# RectifierPartOne.net
KiCad netlist of a schematic drawn in EAGLE
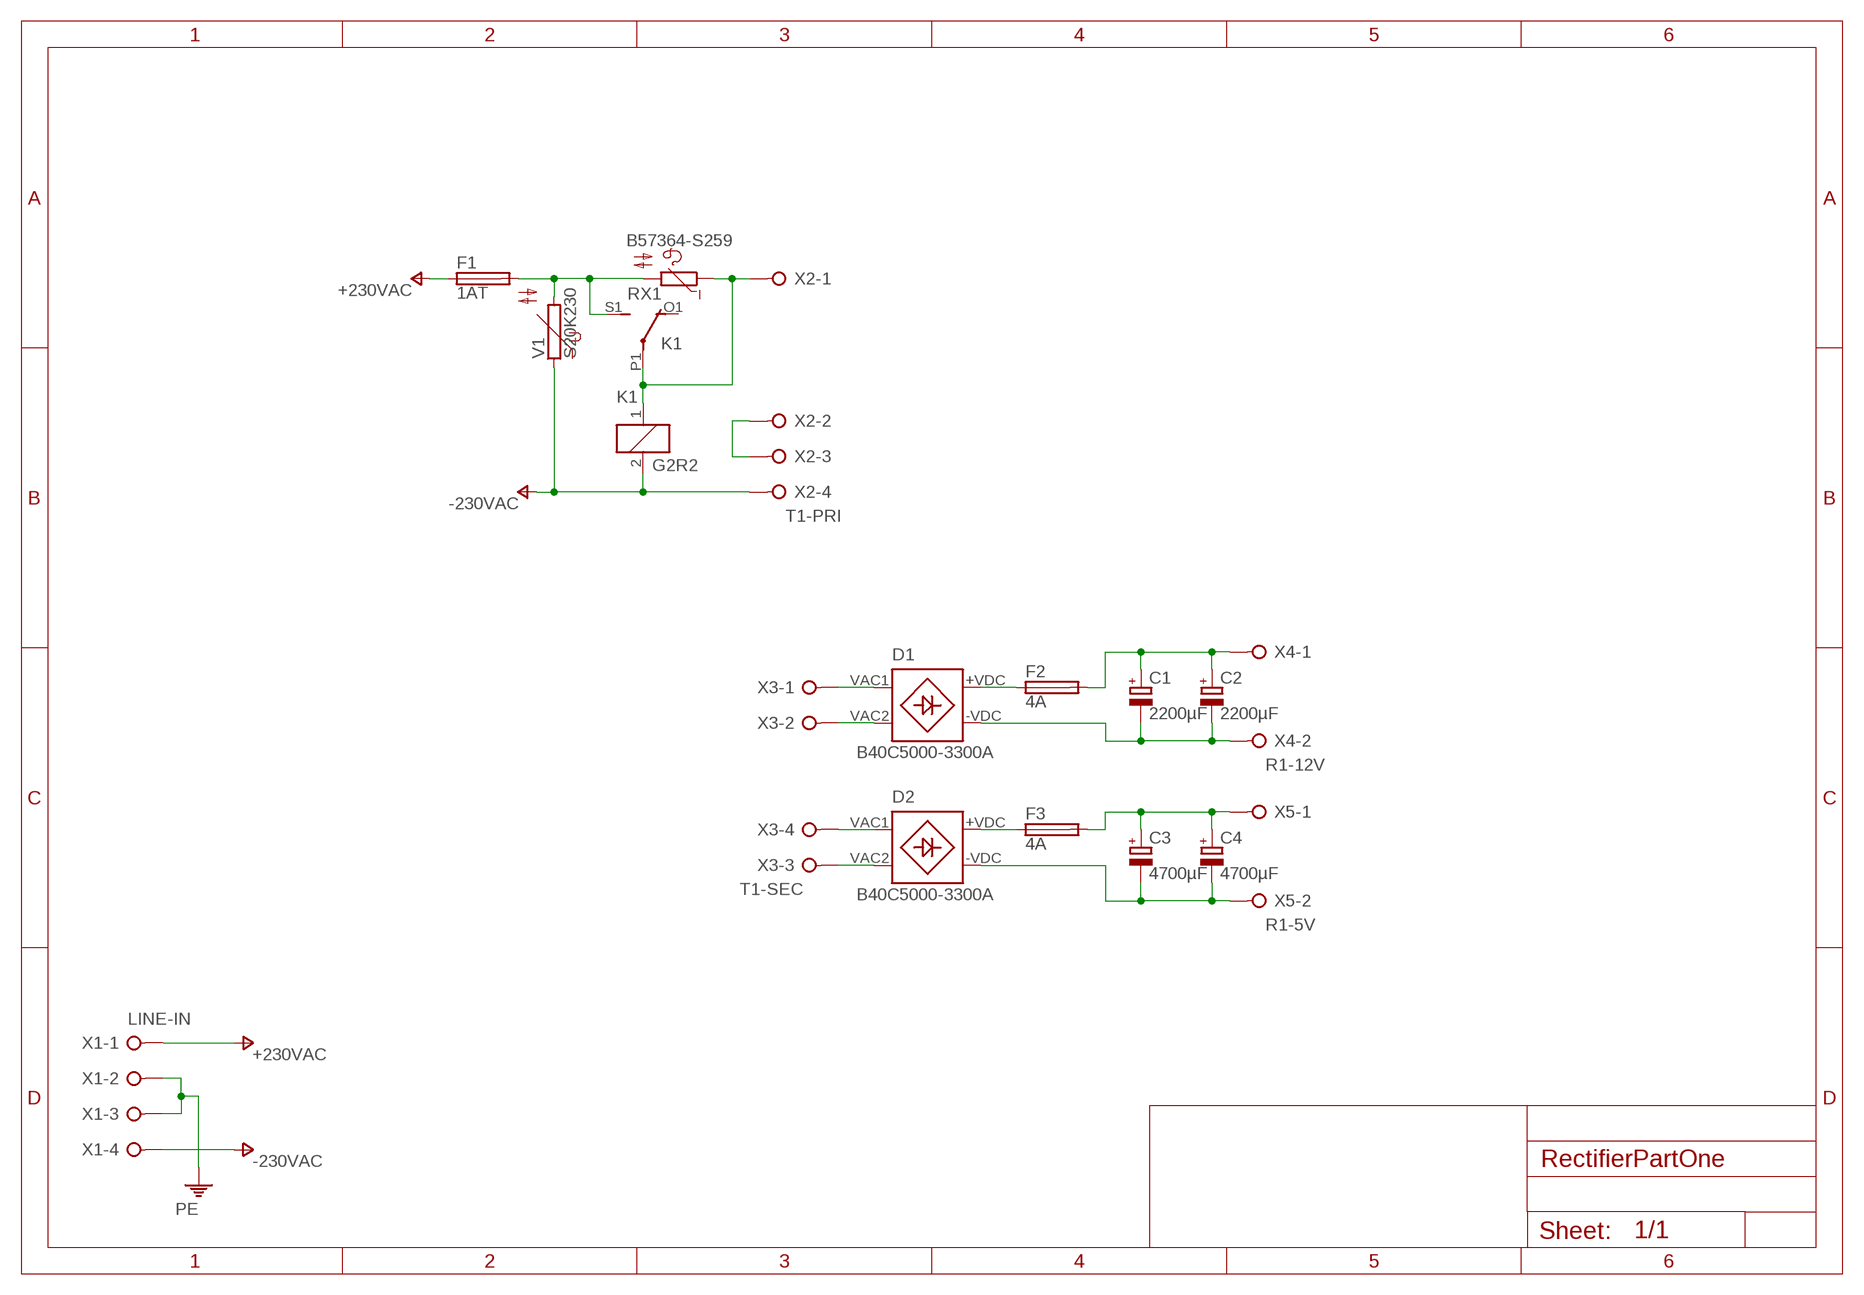
[diagram p0: schematic, sheet 1]

(export (version "E")
  (design (tool "Eeschema 10.0.6"))
  (components
    (comp (ref "C1")
      (value "2200µF")
      (footprint "eagle-import:E7,5-16")
      (libsource (lib "eagle-import") (part "CPOL-EUE7.5-16"))
    )
    (comp (ref "C2")
      (value "2200µF")
      (footprint "eagle-import:E7,5-16")
      (libsource (lib "eagle-import") (part "CPOL-EUE7.5-16"))
    )
    (comp (ref "C3")
      (value "4700µF")
      (footprint "eagle-import:E7,5-16")
      (libsource (lib "eagle-import") (part "CPOL-EUE7.5-16"))
    )
    (comp (ref "C4")
      (value "4700µF")
      (footprint "eagle-import:E7,5-16")
      (libsource (lib "eagle-import") (part "CPOL-EUE7.5-16"))
    )
    (comp (ref "D1")
      (value "B40C5000-3300A")
      (footprint "eagle-import:B..C")
      (libsource (lib "eagle-import") (part "B40C5000-3300A"))
    )
    (comp (ref "D2")
      (value "B40C5000-3300A")
      (footprint "eagle-import:B..C")
      (libsource (lib "eagle-import") (part "B40C5000-3300A"))
    )
    (comp (ref "F1")
      (value "1AT")
      (footprint "eagle-import:SH22,5A")
      (fields (field (name "MPN") "0031.7701.11"))
      (libsource (lib "eagle-import") (part "SH22,5A"))
    )
    (comp (ref "F2")
      (value "4A")
      (footprint "eagle-import:SH22,5A")
      (fields (field (name "MPN") "0031.7701.11"))
      (libsource (lib "eagle-import") (part "SH22,5A"))
    )
    (comp (ref "F3")
      (value "4A")
      (footprint "eagle-import:SH22,5A")
      (fields (field (name "MPN") "0031.7701.11"))
      (libsource (lib "eagle-import") (part "SH22,5A"))
    )
    (comp (ref "K1")
      (value "G2R2")
      (footprint "eagle-import:G2R2")
      (fields (field (name "MF") "OMRON COMPONENTS USA") (field (name "MPN") "G2R-2-DC6"))
      (libsource (lib "eagle-import") (part "G2R2"))
    )
    (comp (ref "RX1")
      (value "B57364-S259")
      (footprint "eagle-import:B57364S0")
      (libsource (lib "eagle-import") (part "EPCB57364-S259"))
    )
    (comp (ref "V1")
      (value "S20K230")
      (footprint "eagle-import:S20K230")
      (libsource (lib "eagle-import") (part "S20K230"))
    )
    (comp (ref "X1")
      (value "LINE-IN")
      (footprint "eagle-import:W237-4P")
      (libsource (lib "eagle-import") (part "W237-04P"))
    )
    (comp (ref "X2")
      (value "T1-PRI")
      (footprint "eagle-import:W237-4P")
      (libsource (lib "eagle-import") (part "W237-04P"))
    )
    (comp (ref "X3")
      (value "T1-SEC")
      (footprint "eagle-import:W237-4P")
      (libsource (lib "eagle-import") (part "W237-04P"))
    )
    (comp (ref "X4")
      (value "R1-12V")
      (footprint "eagle-import:W237-132")
      (libsource (lib "eagle-import") (part "W237-02P"))
    )
    (comp (ref "X5")
      (value "R1-5V")
      (footprint "eagle-import:W237-132")
      (libsource (lib "eagle-import") (part "W237-02P"))
    )
  )
  (nets
    (net (code "1") (name "+230VAC") (class "Default")
      (node (ref "F1") (pin "1") (pinfunction "1_1") (pintype "passive"))
      (node (ref "X1") (pin "1") (pinfunction "KL_1") (pintype "passive"))
    )
    (net (code "2") (name "-230VAC") (class "Default")
      (node (ref "K1") (pin "2") (pinfunction "2_2") (pintype "passive"))
      (node (ref "V1") (pin "1") (pinfunction "1_1") (pintype "passive"))
      (node (ref "X1") (pin "4") (pinfunction "KL_4") (pintype "passive"))
      (node (ref "X2") (pin "4") (pinfunction "KL_4") (pintype "passive"))
    )
    (net (code "3") (name "Net-(D1-Pad+VDC)") (class "Default")
      (node (ref "D1") (pin "+VDC") (pinfunction "+VDC_+VDC") (pintype "output"))
      (node (ref "F2") (pin "1") (pinfunction "1_1") (pintype "passive"))
    )
    (net (code "4") (name "Net-(D2-Pad+VDC)") (class "Default")
      (node (ref "D2") (pin "+VDC") (pinfunction "+VDC_+VDC") (pintype "output"))
      (node (ref "F3") (pin "1") (pinfunction "1_1") (pintype "passive"))
    )
    (net (code "5") (name "Net-(K1B-P)") (class "Default")
      (node (ref "K1") (pin "1") (pinfunction "1_1") (pintype "passive"))
      (node (ref "K1") (pin "P1") (pinfunction "P_P1") (pintype "passive"))
      (node (ref "RX1") (pin "P$1") (pinfunction "1_P$1") (pintype "passive"))
      (node (ref "X2") (pin "1") (pinfunction "KL_1") (pintype "passive"))
    )
    (net (code "6") (name "Net-(K1B-S)") (class "Default")
      (node (ref "F1") (pin "2") (pinfunction "2_2") (pintype "passive"))
      (node (ref "K1") (pin "S1") (pinfunction "S_S1") (pintype "passive"))
      (node (ref "RX1") (pin "P$2") (pinfunction "2_P$2") (pintype "passive"))
      (node (ref "V1") (pin "2") (pinfunction "2_2") (pintype "passive"))
    )
    (net (code "7") (name "Net-(X2B-KL)") (class "Default")
      (node (ref "X2") (pin "2") (pinfunction "KL_2") (pintype "passive"))
      (node (ref "X2") (pin "3") (pinfunction "KL_3") (pintype "passive"))
    )
    (net (code "8") (name "Net-(X3A-KL)") (class "Default")
      (node (ref "D1") (pin "VAC1") (pinfunction "VAC1_VAC1") (pintype "input"))
      (node (ref "X3") (pin "1") (pinfunction "KL_1") (pintype "passive"))
    )
    (net (code "9") (name "Net-(X3B-KL)") (class "Default")
      (node (ref "D1") (pin "VAC2") (pinfunction "VAC2_VAC2") (pintype "input"))
      (node (ref "X3") (pin "2") (pinfunction "KL_2") (pintype "passive"))
    )
    (net (code "10") (name "Net-(X3C-KL)") (class "Default")
      (node (ref "D2") (pin "VAC2") (pinfunction "VAC2_VAC2") (pintype "input"))
      (node (ref "X3") (pin "3") (pinfunction "KL_3") (pintype "passive"))
    )
    (net (code "11") (name "Net-(X3D-KL)") (class "Default")
      (node (ref "D2") (pin "VAC1") (pinfunction "VAC1_VAC1") (pintype "input"))
      (node (ref "X3") (pin "4") (pinfunction "KL_4") (pintype "passive"))
    )
    (net (code "12") (name "Net-(X4A-KL)") (class "Default")
      (node (ref "C1") (pin "+") (pinfunction "+_+") (pintype "passive"))
      (node (ref "C2") (pin "+") (pinfunction "+_+") (pintype "passive"))
      (node (ref "F2") (pin "2") (pinfunction "2_2") (pintype "passive"))
      (node (ref "X4") (pin "1") (pinfunction "KL_1") (pintype "passive"))
    )
    (net (code "13") (name "Net-(X4B-KL)") (class "Default")
      (node (ref "C1") (pin "-") (pinfunction "-_-") (pintype "passive"))
      (node (ref "C2") (pin "-") (pinfunction "-_-") (pintype "passive"))
      (node (ref "D1") (pin "-VDC") (pinfunction "-VDC_-VDC") (pintype "output"))
      (node (ref "X4") (pin "2") (pinfunction "KL_2") (pintype "passive"))
    )
    (net (code "14") (name "Net-(X5A-KL)") (class "Default")
      (node (ref "C3") (pin "+") (pinfunction "+_+") (pintype "passive"))
      (node (ref "C4") (pin "+") (pinfunction "+_+") (pintype "passive"))
      (node (ref "F3") (pin "2") (pinfunction "2_2") (pintype "passive"))
      (node (ref "X5") (pin "1") (pinfunction "KL_1") (pintype "passive"))
    )
    (net (code "15") (name "Net-(X5B-KL)") (class "Default")
      (node (ref "C3") (pin "-") (pinfunction "-_-") (pintype "passive"))
      (node (ref "C4") (pin "-") (pinfunction "-_-") (pintype "passive"))
      (node (ref "D2") (pin "-VDC") (pinfunction "-VDC_-VDC") (pintype "output"))
      (node (ref "X5") (pin "2") (pinfunction "KL_2") (pintype "passive"))
    )
    (net (code "16") (name "PE") (class "Default")
      (node (ref "X1") (pin "2") (pinfunction "KL_2") (pintype "passive"))
      (node (ref "X1") (pin "3") (pinfunction "KL_3") (pintype "passive"))
    )
    (net (code "17") (name "unconnected-(K1B-O-PadO1)") (class "Default")
      (node (ref "K1") (pin "O1") (pinfunction "O_O1") (pintype "passive"))
    )
  )
)
